# 4017_Module.net
KiCad netlist of a schematic drawn in EAGLE
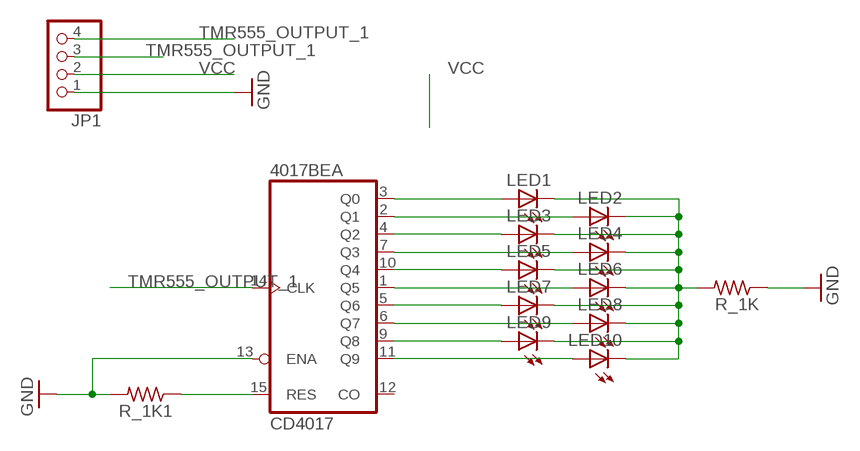
[diagram p0: schematic, sheet 1]

(export (version "E")
  (design (tool "Eeschema 10.0.6"))
  (components
    (comp (ref "4017BE")
      (value "CD4017")
      (footprint "eagle-import:DIL16")
      (libsource (lib "eagle-import") (part "CD4017"))
    )
    (comp (ref "JP1")
      (value "PINHD-1X4")
      (footprint "eagle-import:1X04")
      (libsource (lib "eagle-import") (part "PINHD-1X4"))
    )
    (comp (ref "LED1")
      (value "LEDSMT1206")
      (footprint "eagle-import:1206")
      (libsource (lib "eagle-import") (part "LEDSMT1206"))
    )
    (comp (ref "LED2")
      (value "LEDSMT1206")
      (footprint "eagle-import:1206")
      (libsource (lib "eagle-import") (part "LEDSMT1206"))
    )
    (comp (ref "LED3")
      (value "LEDSMT1206")
      (footprint "eagle-import:1206")
      (libsource (lib "eagle-import") (part "LEDSMT1206"))
    )
    (comp (ref "LED4")
      (value "LEDSMT1206")
      (footprint "eagle-import:1206")
      (libsource (lib "eagle-import") (part "LEDSMT1206"))
    )
    (comp (ref "LED5")
      (value "LEDSMT1206")
      (footprint "eagle-import:1206")
      (libsource (lib "eagle-import") (part "LEDSMT1206"))
    )
    (comp (ref "LED6")
      (value "LEDSMT1206")
      (footprint "eagle-import:1206")
      (libsource (lib "eagle-import") (part "LEDSMT1206"))
    )
    (comp (ref "LED7")
      (value "LEDSMT1206")
      (footprint "eagle-import:1206")
      (libsource (lib "eagle-import") (part "LEDSMT1206"))
    )
    (comp (ref "LED8")
      (value "LEDSMT1206")
      (footprint "eagle-import:1206")
      (libsource (lib "eagle-import") (part "LEDSMT1206"))
    )
    (comp (ref "LED9")
      (value "LEDSMT1206")
      (footprint "eagle-import:1206")
      (libsource (lib "eagle-import") (part "LEDSMT1206"))
    )
    (comp (ref "LED10")
      (value "LEDSMT1206")
      (footprint "eagle-import:1206")
      (libsource (lib "eagle-import") (part "LEDSMT1206"))
    )
    (comp (ref "R_1K")
      (value "R-US_R1206")
      (footprint "eagle-import:R1206")
      (libsource (lib "eagle-import") (part "R-US_R1206"))
    )
    (comp (ref "R_1K1")
      (value "R-US_R1206")
      (footprint "eagle-import:R1206")
      (libsource (lib "eagle-import") (part "R-US_R1206"))
    )
  )
  (nets
    (net (code "1") (name "/TMR555_OUTPUT_1") (class "Default")
      (node (ref "4017BE") (pin "14") (pinfunction "CLK_14") (pintype "input"))
      (node (ref "JP1") (pin "3") (pinfunction "3_3") (pintype "passive"))
      (node (ref "JP1") (pin "4") (pinfunction "4_4") (pintype "passive"))
    )
    (net (code "2") (name "/VCC") (class "Default")
      (node (ref "JP1") (pin "2") (pinfunction "2_2") (pintype "passive"))
    )
    (net (code "3") (name "GND") (class "Default")
      (node (ref "4017BE") (pin "13") (pinfunction "ENA_13") (pintype "input"))
      (node (ref "JP1") (pin "1") (pinfunction "1_1") (pintype "passive"))
      (node (ref "R_1K") (pin "1") (pinfunction "1_1") (pintype "passive"))
      (node (ref "R_1K1") (pin "2") (pinfunction "2_2") (pintype "passive"))
    )
    (net (code "4") (name "Net-(4017BEA-Q0)") (class "Default")
      (node (ref "4017BE") (pin "3") (pinfunction "Q0_3") (pintype "output"))
      (node (ref "LED1") (pin "A") (pinfunction "A_A") (pintype "passive"))
    )
    (net (code "5") (name "Net-(4017BEA-Q1)") (class "Default")
      (node (ref "4017BE") (pin "2") (pinfunction "Q1_2") (pintype "output"))
      (node (ref "LED2") (pin "A") (pinfunction "A_A") (pintype "passive"))
    )
    (net (code "6") (name "Net-(4017BEA-Q2)") (class "Default")
      (node (ref "4017BE") (pin "4") (pinfunction "Q2_4") (pintype "output"))
      (node (ref "LED3") (pin "A") (pinfunction "A_A") (pintype "passive"))
    )
    (net (code "7") (name "Net-(4017BEA-Q3)") (class "Default")
      (node (ref "4017BE") (pin "7") (pinfunction "Q3_7") (pintype "output"))
      (node (ref "LED4") (pin "A") (pinfunction "A_A") (pintype "passive"))
    )
    (net (code "8") (name "Net-(4017BEA-Q4)") (class "Default")
      (node (ref "4017BE") (pin "10") (pinfunction "Q4_10") (pintype "output"))
      (node (ref "LED5") (pin "A") (pinfunction "A_A") (pintype "passive"))
    )
    (net (code "9") (name "Net-(4017BEA-Q5)") (class "Default")
      (node (ref "4017BE") (pin "1") (pinfunction "Q5_1") (pintype "output"))
      (node (ref "LED6") (pin "A") (pinfunction "A_A") (pintype "passive"))
    )
    (net (code "10") (name "Net-(4017BEA-Q6)") (class "Default")
      (node (ref "4017BE") (pin "5") (pinfunction "Q6_5") (pintype "output"))
      (node (ref "LED7") (pin "A") (pinfunction "A_A") (pintype "passive"))
    )
    (net (code "11") (name "Net-(4017BEA-Q7)") (class "Default")
      (node (ref "4017BE") (pin "6") (pinfunction "Q7_6") (pintype "output"))
      (node (ref "LED8") (pin "A") (pinfunction "A_A") (pintype "passive"))
    )
    (net (code "12") (name "Net-(4017BEA-Q8)") (class "Default")
      (node (ref "4017BE") (pin "9") (pinfunction "Q8_9") (pintype "output"))
      (node (ref "LED9") (pin "A") (pinfunction "A_A") (pintype "passive"))
    )
    (net (code "13") (name "Net-(4017BEA-Q9)") (class "Default")
      (node (ref "4017BE") (pin "11") (pinfunction "Q9_11") (pintype "output"))
      (node (ref "LED10") (pin "A") (pinfunction "A_A") (pintype "passive"))
    )
    (net (code "14") (name "Net-(4017BEA-RES)") (class "Default")
      (node (ref "4017BE") (pin "15") (pinfunction "RES_15") (pintype "input"))
      (node (ref "R_1K1") (pin "1") (pinfunction "1_1") (pintype "passive"))
    )
    (net (code "15") (name "Net-(LED1-PadC)") (class "Default")
      (node (ref "LED1") (pin "C") (pinfunction "C_C") (pintype "passive"))
      (node (ref "LED10") (pin "C") (pinfunction "C_C") (pintype "passive"))
      (node (ref "LED2") (pin "C") (pinfunction "C_C") (pintype "passive"))
      (node (ref "LED3") (pin "C") (pinfunction "C_C") (pintype "passive"))
      (node (ref "LED4") (pin "C") (pinfunction "C_C") (pintype "passive"))
      (node (ref "LED5") (pin "C") (pinfunction "C_C") (pintype "passive"))
      (node (ref "LED6") (pin "C") (pinfunction "C_C") (pintype "passive"))
      (node (ref "LED7") (pin "C") (pinfunction "C_C") (pintype "passive"))
      (node (ref "LED8") (pin "C") (pinfunction "C_C") (pintype "passive"))
      (node (ref "LED9") (pin "C") (pinfunction "C_C") (pintype "passive"))
      (node (ref "R_1K") (pin "2") (pinfunction "2_2") (pintype "passive"))
    )
    (net (code "16") (name "unconnected-(4017BEA-CO-Pad12)") (class "Default")
      (node (ref "4017BE") (pin "12") (pinfunction "CO_12") (pintype "output"))
    )
  )
)
